# cv_led.net
KiCad netlist of a schematic drawn in EAGLE
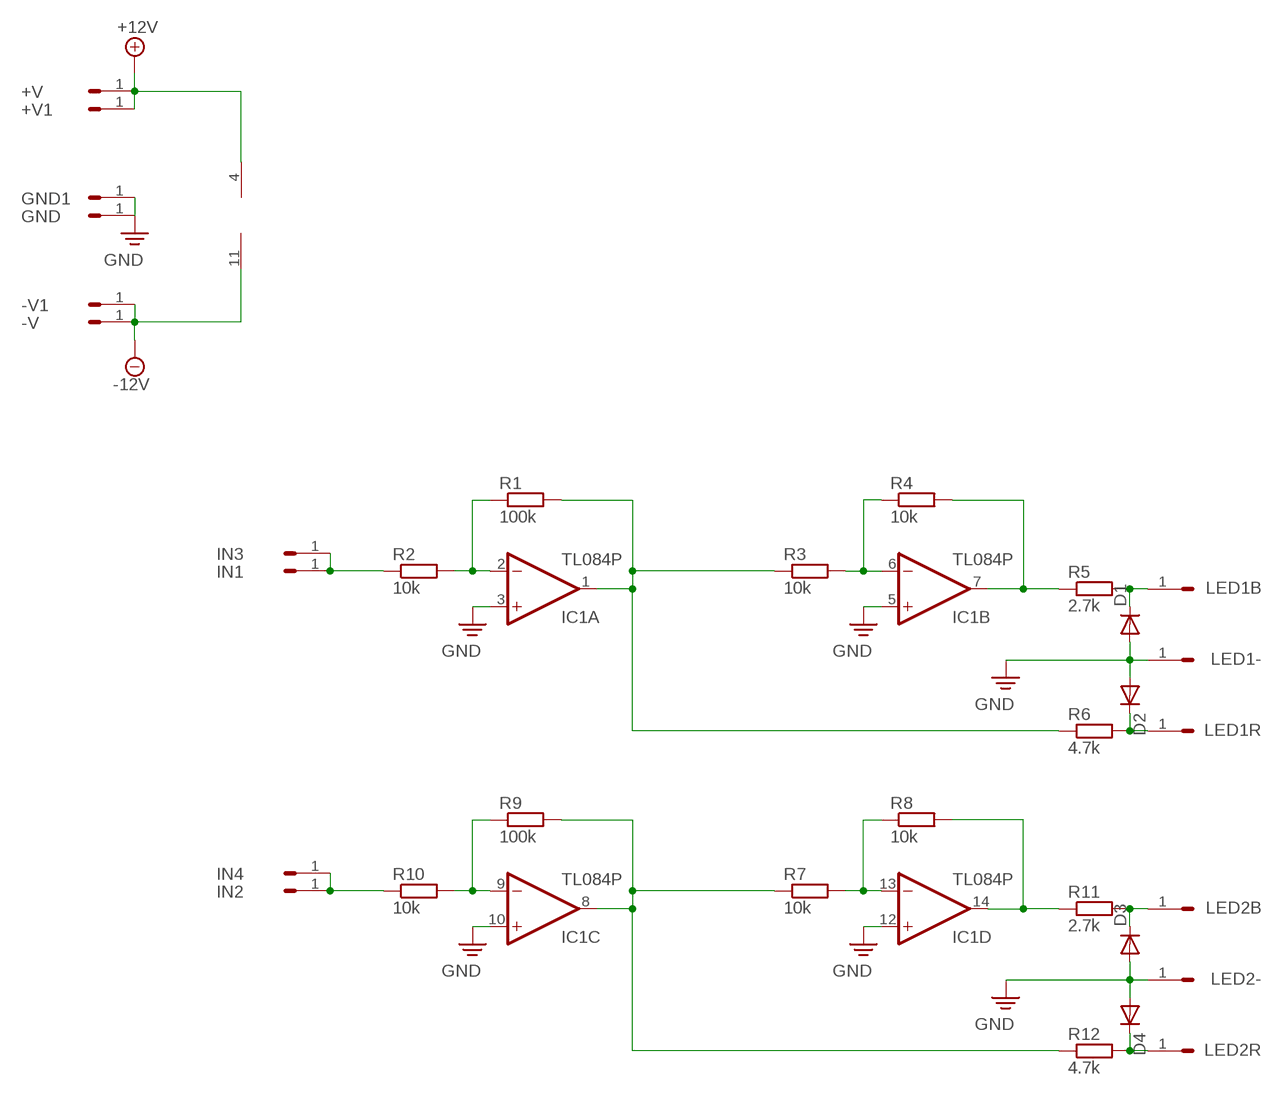
[diagram p0: schematic, sheet 1]

(export (version "E")
  (design (tool "Eeschema 10.0.6"))
  (components
    (comp (ref "+V")
      (value "HEADER/MALE/01")
      (footprint "eagle-import:HEADER_MALE_01")
      (fields (field (name "SPICEPREFIX") "X"))
      (libsource (lib "eagle-import") (part "HEADER/MALE/01"))
    )
    (comp (ref "+V1")
      (value "HEADER/MALE/01")
      (footprint "eagle-import:HEADER_MALE_01")
      (fields (field (name "SPICEPREFIX") "X"))
      (libsource (lib "eagle-import") (part "HEADER/MALE/01"))
    )
    (comp (ref "-V")
      (value "HEADER/MALE/01")
      (footprint "eagle-import:HEADER_MALE_01")
      (fields (field (name "SPICEPREFIX") "X"))
      (libsource (lib "eagle-import") (part "HEADER/MALE/01"))
    )
    (comp (ref "-V1")
      (value "HEADER/MALE/01")
      (footprint "eagle-import:HEADER_MALE_01")
      (fields (field (name "SPICEPREFIX") "X"))
      (libsource (lib "eagle-import") (part "HEADER/MALE/01"))
    )
    (comp (ref "D1")
      (value "1N4148DO35-7")
      (footprint "eagle-import:DO35-7")
      (libsource (lib "eagle-import") (part "1N4148DO35-7"))
    )
    (comp (ref "D2")
      (value "1N4148DO35-7")
      (footprint "eagle-import:DO35-7")
      (libsource (lib "eagle-import") (part "1N4148DO35-7"))
    )
    (comp (ref "D3")
      (value "1N4148DO35-7")
      (footprint "eagle-import:DO35-7")
      (libsource (lib "eagle-import") (part "1N4148DO35-7"))
    )
    (comp (ref "D4")
      (value "1N4148DO35-7")
      (footprint "eagle-import:DO35-7")
      (libsource (lib "eagle-import") (part "1N4148DO35-7"))
    )
    (comp (ref "GND")
      (value "HEADER/MALE/01")
      (footprint "eagle-import:HEADER_MALE_01")
      (fields (field (name "SPICEPREFIX") "X"))
      (libsource (lib "eagle-import") (part "HEADER/MALE/01"))
    )
    (comp (ref "GND1")
      (value "HEADER/MALE/01")
      (footprint "eagle-import:HEADER_MALE_01")
      (fields (field (name "SPICEPREFIX") "X"))
      (libsource (lib "eagle-import") (part "HEADER/MALE/01"))
    )
    (comp (ref "IC1")
      (value "TL084P")
      (footprint "eagle-import:DIL14")
      (libsource (lib "eagle-import") (part "TL084P"))
    )
    (comp (ref "IN1")
      (value "HEADER/MALE/01")
      (footprint "eagle-import:HEADER_MALE_01")
      (fields (field (name "SPICEPREFIX") "X"))
      (libsource (lib "eagle-import") (part "HEADER/MALE/01"))
    )
    (comp (ref "IN2")
      (value "HEADER/MALE/01")
      (footprint "eagle-import:HEADER_MALE_01")
      (fields (field (name "SPICEPREFIX") "X"))
      (libsource (lib "eagle-import") (part "HEADER/MALE/01"))
    )
    (comp (ref "IN3")
      (value "HEADER/MALE/01")
      (footprint "eagle-import:HEADER_MALE_01")
      (fields (field (name "SPICEPREFIX") "X"))
      (libsource (lib "eagle-import") (part "HEADER/MALE/01"))
    )
    (comp (ref "IN4")
      (value "HEADER/MALE/01")
      (footprint "eagle-import:HEADER_MALE_01")
      (fields (field (name "SPICEPREFIX") "X"))
      (libsource (lib "eagle-import") (part "HEADER/MALE/01"))
    )
    (comp (ref "LED1-")
      (value "HEADER/MALE/01")
      (footprint "eagle-import:HEADER_MALE_01")
      (fields (field (name "SPICEPREFIX") "X"))
      (libsource (lib "eagle-import") (part "HEADER/MALE/01"))
    )
    (comp (ref "LED1B")
      (value "HEADER/MALE/01")
      (footprint "eagle-import:HEADER_MALE_01")
      (fields (field (name "SPICEPREFIX") "X"))
      (libsource (lib "eagle-import") (part "HEADER/MALE/01"))
    )
    (comp (ref "LED1R")
      (value "HEADER/MALE/01")
      (footprint "eagle-import:HEADER_MALE_01")
      (fields (field (name "SPICEPREFIX") "X"))
      (libsource (lib "eagle-import") (part "HEADER/MALE/01"))
    )
    (comp (ref "LED2-")
      (value "HEADER/MALE/01")
      (footprint "eagle-import:HEADER_MALE_01")
      (fields (field (name "SPICEPREFIX") "X"))
      (libsource (lib "eagle-import") (part "HEADER/MALE/01"))
    )
    (comp (ref "LED2B")
      (value "HEADER/MALE/01")
      (footprint "eagle-import:HEADER_MALE_01")
      (fields (field (name "SPICEPREFIX") "X"))
      (libsource (lib "eagle-import") (part "HEADER/MALE/01"))
    )
    (comp (ref "LED2R")
      (value "HEADER/MALE/01")
      (footprint "eagle-import:HEADER_MALE_01")
      (fields (field (name "SPICEPREFIX") "X"))
      (libsource (lib "eagle-import") (part "HEADER/MALE/01"))
    )
    (comp (ref "R1")
      (value "100k")
      (footprint "eagle-import:RESISTOR_7.5")
      (libsource (lib "eagle-import") (part "RESISTORRESISTOR/UPRIGHT/7.5"))
    )
    (comp (ref "R2")
      (value "10k")
      (footprint "eagle-import:RESISTOR_7.5")
      (libsource (lib "eagle-import") (part "RESISTORRESISTOR/UPRIGHT/7.5"))
    )
    (comp (ref "R3")
      (value "10k")
      (footprint "eagle-import:RESISTOR_7.5")
      (libsource (lib "eagle-import") (part "RESISTORRESISTOR/UPRIGHT/7.5"))
    )
    (comp (ref "R4")
      (value "10k")
      (footprint "eagle-import:RESISTOR_7.5")
      (libsource (lib "eagle-import") (part "RESISTORRESISTOR/UPRIGHT/7.5"))
    )
    (comp (ref "R5")
      (value "2.7k")
      (footprint "eagle-import:RESISTOR_7.5")
      (libsource (lib "eagle-import") (part "RESISTORRESISTOR/UPRIGHT/7.5"))
    )
    (comp (ref "R6")
      (value "4.7k")
      (footprint "eagle-import:RESISTOR_7.5")
      (libsource (lib "eagle-import") (part "RESISTORRESISTOR/UPRIGHT/7.5"))
    )
    (comp (ref "R7")
      (value "10k")
      (footprint "eagle-import:RESISTOR_7.5")
      (libsource (lib "eagle-import") (part "RESISTORRESISTOR/UPRIGHT/7.5"))
    )
    (comp (ref "R8")
      (value "10k")
      (footprint "eagle-import:RESISTOR_7.5")
      (libsource (lib "eagle-import") (part "RESISTORRESISTOR/UPRIGHT/7.5"))
    )
    (comp (ref "R9")
      (value "100k")
      (footprint "eagle-import:RESISTOR_7.5")
      (libsource (lib "eagle-import") (part "RESISTORRESISTOR/UPRIGHT/7.5"))
    )
    (comp (ref "R10")
      (value "10k")
      (footprint "eagle-import:RESISTOR_7.5")
      (libsource (lib "eagle-import") (part "RESISTORRESISTOR/UPRIGHT/7.5"))
    )
    (comp (ref "R11")
      (value "2.7k")
      (footprint "eagle-import:RESISTOR_7.5")
      (libsource (lib "eagle-import") (part "RESISTORRESISTOR/UPRIGHT/7.5"))
    )
    (comp (ref "R12")
      (value "4.7k")
      (footprint "eagle-import:RESISTOR_7.5")
      (libsource (lib "eagle-import") (part "RESISTORRESISTOR/UPRIGHT/7.5"))
    )
  )
  (nets
    (net (code "1") (name "+12V") (class "Default")
      (node (ref "+V") (pin "1") (pinfunction "3_1") (pintype "passive"))
      (node (ref "+V1") (pin "1") (pinfunction "3_1") (pintype "passive"))
      (node (ref "IC1") (pin "4") (pinfunction "V+_4") (pintype "power_in"))
    )
    (net (code "2") (name "-12V") (class "Default")
      (node (ref "-V") (pin "1") (pinfunction "3_1") (pintype "passive"))
      (node (ref "-V1") (pin "1") (pinfunction "3_1") (pintype "passive"))
      (node (ref "IC1") (pin "11") (pinfunction "V-_11") (pintype "power_in"))
    )
    (net (code "3") (name "GND") (class "Default")
      (node (ref "D1") (pin "A") (pinfunction "A_A") (pintype "passive"))
      (node (ref "D2") (pin "A") (pinfunction "A_A") (pintype "passive"))
      (node (ref "D3") (pin "A") (pinfunction "A_A") (pintype "passive"))
      (node (ref "D4") (pin "A") (pinfunction "A_A") (pintype "passive"))
      (node (ref "GND") (pin "1") (pinfunction "3_1") (pintype "passive"))
      (node (ref "GND1") (pin "1") (pinfunction "3_1") (pintype "passive"))
      (node (ref "IC1") (pin "10") (pinfunction "+IN_10") (pintype "input"))
      (node (ref "IC1") (pin "12") (pinfunction "+IN_12") (pintype "input"))
      (node (ref "IC1") (pin "3") (pinfunction "+IN_3") (pintype "input"))
      (node (ref "IC1") (pin "5") (pinfunction "+IN_5") (pintype "input"))
      (node (ref "LED1-") (pin "1") (pinfunction "3_1") (pintype "passive"))
      (node (ref "LED2-") (pin "1") (pinfunction "3_1") (pintype "passive"))
    )
    (net (code "4") (name "Net-(IC1A--IN)") (class "Default")
      (node (ref "IC1") (pin "2") (pinfunction "-IN_2") (pintype "input"))
      (node (ref "R1") (pin "1") (pinfunction "1_1") (pintype "passive"))
      (node (ref "R2") (pin "2") (pinfunction "2_2") (pintype "passive"))
    )
    (net (code "5") (name "Net-(IC1A-OUT)") (class "Default")
      (node (ref "IC1") (pin "1") (pinfunction "OUT_1") (pintype "output"))
      (node (ref "R1") (pin "2") (pinfunction "2_2") (pintype "passive"))
      (node (ref "R3") (pin "1") (pinfunction "1_1") (pintype "passive"))
      (node (ref "R6") (pin "1") (pinfunction "1_1") (pintype "passive"))
    )
    (net (code "6") (name "Net-(IC1B--IN)") (class "Default")
      (node (ref "IC1") (pin "6") (pinfunction "-IN_6") (pintype "input"))
      (node (ref "R3") (pin "2") (pinfunction "2_2") (pintype "passive"))
      (node (ref "R4") (pin "1") (pinfunction "1_1") (pintype "passive"))
    )
    (net (code "7") (name "Net-(IC1B-OUT)") (class "Default")
      (node (ref "IC1") (pin "7") (pinfunction "OUT_7") (pintype "output"))
      (node (ref "R4") (pin "2") (pinfunction "2_2") (pintype "passive"))
      (node (ref "R5") (pin "1") (pinfunction "1_1") (pintype "passive"))
    )
    (net (code "8") (name "Net-(IC1C--IN)") (class "Default")
      (node (ref "IC1") (pin "9") (pinfunction "-IN_9") (pintype "input"))
      (node (ref "R10") (pin "2") (pinfunction "2_2") (pintype "passive"))
      (node (ref "R9") (pin "1") (pinfunction "1_1") (pintype "passive"))
    )
    (net (code "9") (name "Net-(IC1C-OUT)") (class "Default")
      (node (ref "IC1") (pin "8") (pinfunction "OUT_8") (pintype "output"))
      (node (ref "R12") (pin "1") (pinfunction "1_1") (pintype "passive"))
      (node (ref "R7") (pin "1") (pinfunction "1_1") (pintype "passive"))
      (node (ref "R9") (pin "2") (pinfunction "2_2") (pintype "passive"))
    )
    (net (code "10") (name "Net-(IC1D--IN)") (class "Default")
      (node (ref "IC1") (pin "13") (pinfunction "-IN_13") (pintype "input"))
      (node (ref "R7") (pin "2") (pinfunction "2_2") (pintype "passive"))
      (node (ref "R8") (pin "1") (pinfunction "1_1") (pintype "passive"))
    )
    (net (code "11") (name "Net-(IC1D-OUT)") (class "Default")
      (node (ref "IC1") (pin "14") (pinfunction "OUT_14") (pintype "output"))
      (node (ref "R11") (pin "1") (pinfunction "1_1") (pintype "passive"))
      (node (ref "R8") (pin "2") (pinfunction "2_2") (pintype "passive"))
    )
    (net (code "12") (name "Net-(IN1-3)") (class "Default")
      (node (ref "IN1") (pin "1") (pinfunction "3_1") (pintype "passive"))
      (node (ref "IN3") (pin "1") (pinfunction "3_1") (pintype "passive"))
      (node (ref "R2") (pin "1") (pinfunction "1_1") (pintype "passive"))
    )
    (net (code "13") (name "Net-(IN2-3)") (class "Default")
      (node (ref "IN2") (pin "1") (pinfunction "3_1") (pintype "passive"))
      (node (ref "IN4") (pin "1") (pinfunction "3_1") (pintype "passive"))
      (node (ref "R10") (pin "1") (pinfunction "1_1") (pintype "passive"))
    )
    (net (code "14") (name "Net-(LED1B-3)") (class "Default")
      (node (ref "D1") (pin "C") (pinfunction "C_C") (pintype "passive"))
      (node (ref "LED1B") (pin "1") (pinfunction "3_1") (pintype "passive"))
      (node (ref "R5") (pin "2") (pinfunction "2_2") (pintype "passive"))
    )
    (net (code "15") (name "Net-(LED1R-3)") (class "Default")
      (node (ref "D2") (pin "C") (pinfunction "C_C") (pintype "passive"))
      (node (ref "LED1R") (pin "1") (pinfunction "3_1") (pintype "passive"))
      (node (ref "R6") (pin "2") (pinfunction "2_2") (pintype "passive"))
    )
    (net (code "16") (name "Net-(LED2B-3)") (class "Default")
      (node (ref "D3") (pin "C") (pinfunction "C_C") (pintype "passive"))
      (node (ref "LED2B") (pin "1") (pinfunction "3_1") (pintype "passive"))
      (node (ref "R11") (pin "2") (pinfunction "2_2") (pintype "passive"))
    )
    (net (code "17") (name "Net-(LED2R-3)") (class "Default")
      (node (ref "D4") (pin "C") (pinfunction "C_C") (pintype "passive"))
      (node (ref "LED2R") (pin "1") (pinfunction "3_1") (pintype "passive"))
      (node (ref "R12") (pin "2") (pinfunction "2_2") (pintype "passive"))
    )
  )
)
